# I2C_SW.net
KiCad netlist of a schematic drawn in Altium Designer
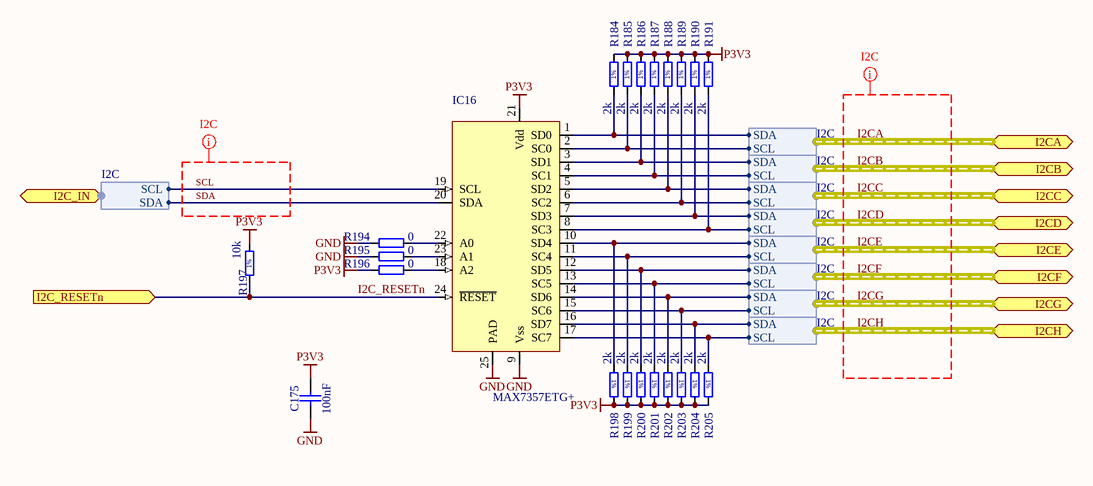
[diagram p0: I2C_SW.SchDoc]

(export (version "E")
  (design (tool "Eeschema 10.0.6"))
  (components
    (comp (ref "C175")
      (value "100nF")
      (footprint "CAPC1005X55N")
      (description "Non-polarised capacitor")
      (fields
        (field (name "PART NUMBER") "CC0402_100NF_16V_10%_X5R")
        (field (name "VOLTAGE") "16V")
        (field (name "AUTHOR") "CERN DEM JLC")
      )
      (libsource (lib "Capacitors") (part "Capacitor - non polarized"))
    )
    (comp (ref "IC16")
      (value "MAX7357ETG+")
      (footprint "HVQFN24")
      (description "8-channel I2C-bus multiplexer with reset, INT and timeout")
      (libsource (lib "LIBRARY_SCH") (part "IIC_MUX_MAX7357ETG+"))
    )
    (comp (ref "R184")
      (value "2k")
      (footprint "RESC1005X40N")
      (description "Resistor - 1%")
      (fields
        (field (name "PART NUMBER") "R0402_2K_1%_0.0625W_100PPM")
        (field (name "POWER") "0.0625W")
        (field (name "AUTHOR") "CERN DEM JLC")
      )
      (libsource (lib "Resistors") (part "Resistor - 1%"))
    )
    (comp (ref "R185")
      (value "2k")
      (footprint "RESC1005X40N")
      (description "Resistor - 1%")
      (fields
        (field (name "PART NUMBER") "R0402_2K_1%_0.0625W_100PPM")
        (field (name "POWER") "0.0625W")
        (field (name "AUTHOR") "CERN DEM JLC")
      )
      (libsource (lib "Resistors") (part "Resistor - 1%"))
    )
    (comp (ref "R186")
      (value "2k")
      (footprint "RESC1005X40N")
      (description "Resistor - 1%")
      (fields
        (field (name "PART NUMBER") "R0402_2K_1%_0.0625W_100PPM")
        (field (name "POWER") "0.0625W")
        (field (name "AUTHOR") "CERN DEM JLC")
      )
      (libsource (lib "Resistors") (part "Resistor - 1%"))
    )
    (comp (ref "R187")
      (value "2k")
      (footprint "RESC1005X40N")
      (description "Resistor - 1%")
      (fields
        (field (name "PART NUMBER") "R0402_2K_1%_0.0625W_100PPM")
        (field (name "POWER") "0.0625W")
        (field (name "AUTHOR") "CERN DEM JLC")
      )
      (libsource (lib "Resistors") (part "Resistor - 1%"))
    )
    (comp (ref "R188")
      (value "2k")
      (footprint "RESC1005X40N")
      (description "Resistor - 1%")
      (fields
        (field (name "PART NUMBER") "R0402_2K_1%_0.0625W_100PPM")
        (field (name "POWER") "0.0625W")
        (field (name "AUTHOR") "CERN DEM JLC")
      )
      (libsource (lib "Resistors") (part "Resistor - 1%"))
    )
    (comp (ref "R189")
      (value "2k")
      (footprint "RESC1005X40N")
      (description "Resistor - 1%")
      (fields
        (field (name "PART NUMBER") "R0402_2K_1%_0.0625W_100PPM")
        (field (name "POWER") "0.0625W")
        (field (name "AUTHOR") "CERN DEM JLC")
      )
      (libsource (lib "Resistors") (part "Resistor - 1%"))
    )
    (comp (ref "R190")
      (value "2k")
      (footprint "RESC1005X40N")
      (description "Resistor - 1%")
      (fields
        (field (name "PART NUMBER") "R0402_2K_1%_0.0625W_100PPM")
        (field (name "POWER") "0.0625W")
        (field (name "AUTHOR") "CERN DEM JLC")
      )
      (libsource (lib "Resistors") (part "Resistor - 1%"))
    )
    (comp (ref "R191")
      (value "2k")
      (footprint "RESC1005X40N")
      (description "Resistor - 1%")
      (fields
        (field (name "PART NUMBER") "R0402_2K_1%_0.0625W_100PPM")
        (field (name "POWER") "0.0625W")
        (field (name "AUTHOR") "CERN DEM JLC")
      )
      (libsource (lib "Resistors") (part "Resistor - 1%"))
    )
    (comp (ref "R194")
      (value "0")
      (footprint "RESC1005X40N")
      (description "Resistor")
      (fields
        (field (name "PART NUMBER") "R0402_0R_JUMPER")
        (field (name "MANUFACTURER") "GENERIC")
        (field (name "AUTHOR") "CERN DEM JLC")
      )
      (libsource (lib "Resistors") (part "Resistor"))
    )
    (comp (ref "R195")
      (value "0")
      (footprint "RESC1005X40N")
      (description "Resistor")
      (fields
        (field (name "PART NUMBER") "R0402_0R_JUMPER")
        (field (name "MANUFACTURER") "GENERIC")
        (field (name "AUTHOR") "CERN DEM JLC")
      )
      (libsource (lib "Resistors") (part "Resistor"))
    )
    (comp (ref "R196")
      (value "0")
      (footprint "RESC1005X40N")
      (description "Resistor")
      (fields
        (field (name "PART NUMBER") "R0402_0R_JUMPER")
        (field (name "MANUFACTURER") "GENERIC")
        (field (name "AUTHOR") "CERN DEM JLC")
      )
      (libsource (lib "Resistors") (part "Resistor"))
    )
    (comp (ref "R197")
      (value "10k")
      (footprint "RESC1005X40N")
      (description "Resistor - 1%")
      (fields
        (field (name "PART NUMBER") "R0402_10K_1%_0.0625W_100PPM")
        (field (name "POWER") "0.0625W")
        (field (name "AUTHOR") "CERN DEM JLC")
      )
      (libsource (lib "Resistors") (part "Resistor - 1%"))
    )
    (comp (ref "R198")
      (value "2k")
      (footprint "RESC1005X40N")
      (description "Resistor - 1%")
      (fields
        (field (name "PART NUMBER") "R0402_2K_1%_0.0625W_100PPM")
        (field (name "POWER") "0.0625W")
        (field (name "AUTHOR") "CERN DEM JLC")
      )
      (libsource (lib "Resistors") (part "Resistor - 1%"))
    )
    (comp (ref "R199")
      (value "2k")
      (footprint "RESC1005X40N")
      (description "Resistor - 1%")
      (fields
        (field (name "PART NUMBER") "R0402_2K_1%_0.0625W_100PPM")
        (field (name "POWER") "0.0625W")
        (field (name "AUTHOR") "CERN DEM JLC")
      )
      (libsource (lib "Resistors") (part "Resistor - 1%"))
    )
    (comp (ref "R200")
      (value "2k")
      (footprint "RESC1005X40N")
      (description "Resistor - 1%")
      (fields
        (field (name "PART NUMBER") "R0402_2K_1%_0.0625W_100PPM")
        (field (name "POWER") "0.0625W")
        (field (name "AUTHOR") "CERN DEM JLC")
      )
      (libsource (lib "Resistors") (part "Resistor - 1%"))
    )
    (comp (ref "R201")
      (value "2k")
      (footprint "RESC1005X40N")
      (description "Resistor - 1%")
      (fields
        (field (name "PART NUMBER") "R0402_2K_1%_0.0625W_100PPM")
        (field (name "POWER") "0.0625W")
        (field (name "AUTHOR") "CERN DEM JLC")
      )
      (libsource (lib "Resistors") (part "Resistor - 1%"))
    )
    (comp (ref "R202")
      (value "2k")
      (footprint "RESC1005X40N")
      (description "Resistor - 1%")
      (fields
        (field (name "PART NUMBER") "R0402_2K_1%_0.0625W_100PPM")
        (field (name "POWER") "0.0625W")
        (field (name "AUTHOR") "CERN DEM JLC")
      )
      (libsource (lib "Resistors") (part "Resistor - 1%"))
    )
    (comp (ref "R203")
      (value "2k")
      (footprint "RESC1005X40N")
      (description "Resistor - 1%")
      (fields
        (field (name "PART NUMBER") "R0402_2K_1%_0.0625W_100PPM")
        (field (name "POWER") "0.0625W")
        (field (name "AUTHOR") "CERN DEM JLC")
      )
      (libsource (lib "Resistors") (part "Resistor - 1%"))
    )
    (comp (ref "R204")
      (value "2k")
      (footprint "RESC1005X40N")
      (description "Resistor - 1%")
      (fields
        (field (name "PART NUMBER") "R0402_2K_1%_0.0625W_100PPM")
        (field (name "POWER") "0.0625W")
        (field (name "AUTHOR") "CERN DEM JLC")
      )
      (libsource (lib "Resistors") (part "Resistor - 1%"))
    )
    (comp (ref "R205")
      (value "2k")
      (footprint "RESC1005X40N")
      (description "Resistor - 1%")
      (fields
        (field (name "PART NUMBER") "R0402_2K_1%_0.0625W_100PPM")
        (field (name "POWER") "0.0625W")
        (field (name "AUTHOR") "CERN DEM JLC")
      )
      (libsource (lib "Resistors") (part "Resistor - 1%"))
    )
  )
  (nets
    (net (code "18") (name "/I2C_RESETn") (class "Default")
      (node (ref "IC16") (pin "24") (pinfunction "~{RESET}_24") (pintype "input"))
      (node (ref "R197") (pin "1") (pinfunction "1_1") (pintype "passive"))
    )
    (net (code "19") (name "/SCL") (class "Default")
      (node (ref "IC16") (pin "19") (pinfunction "SCL_19") (pintype "input"))
    )
    (net (code "20") (name "/SDA") (class "Default")
      (node (ref "IC16") (pin "20") (pinfunction "SDA_20") (pintype "bidirectional"))
    )
    (net (code "22") (name "GND") (class "Default")
      (node (ref "C175") (pin "1") (pinfunction "1_1") (pintype "passive"))
      (node (ref "IC16") (pin "25") (pinfunction "PAD_25") (pintype "power_in"))
      (node (ref "IC16") (pin "9") (pinfunction "Vss_9") (pintype "power_in"))
      (node (ref "R194") (pin "1") (pinfunction "1_1") (pintype "passive"))
      (node (ref "R195") (pin "1") (pinfunction "1_1") (pintype "passive"))
    )
    (net (code "23") (name "Net-(IC16-A0)") (class "Default")
      (node (ref "IC16") (pin "22") (pinfunction "A0_22") (pintype "input"))
      (node (ref "R194") (pin "2") (pinfunction "2_2") (pintype "passive"))
    )
    (net (code "24") (name "Net-(IC16-A1)") (class "Default")
      (node (ref "IC16") (pin "23") (pinfunction "A1_23") (pintype "input"))
      (node (ref "R195") (pin "2") (pinfunction "2_2") (pintype "passive"))
    )
    (net (code "25") (name "Net-(IC16-A2)") (class "Default")
      (node (ref "IC16") (pin "18") (pinfunction "A2_18") (pintype "input"))
      (node (ref "R196") (pin "2") (pinfunction "2_2") (pintype "passive"))
    )
    (net (code "26") (name "Net-(IC16-SC0)") (class "Default")
      (node (ref "IC16") (pin "2") (pinfunction "SC0_2") (pintype "bidirectional"))
      (node (ref "R185") (pin "1") (pinfunction "1_1") (pintype "passive"))
    )
    (net (code "27") (name "Net-(IC16-SC1)") (class "Default")
      (node (ref "IC16") (pin "4") (pinfunction "SC1_4") (pintype "bidirectional"))
      (node (ref "R187") (pin "1") (pinfunction "1_1") (pintype "passive"))
    )
    (net (code "28") (name "Net-(IC16-SC2)") (class "Default")
      (node (ref "IC16") (pin "6") (pinfunction "SC2_6") (pintype "bidirectional"))
      (node (ref "R189") (pin "1") (pinfunction "1_1") (pintype "passive"))
    )
    (net (code "29") (name "Net-(IC16-SC3)") (class "Default")
      (node (ref "IC16") (pin "8") (pinfunction "SC3_8") (pintype "bidirectional"))
      (node (ref "R191") (pin "1") (pinfunction "1_1") (pintype "passive"))
    )
    (net (code "30") (name "Net-(IC16-SC4)") (class "Default")
      (node (ref "IC16") (pin "11") (pinfunction "SC4_11") (pintype "bidirectional"))
      (node (ref "R199") (pin "1") (pinfunction "1_1") (pintype "passive"))
    )
    (net (code "31") (name "Net-(IC16-SC5)") (class "Default")
      (node (ref "IC16") (pin "13") (pinfunction "SC5_13") (pintype "bidirectional"))
      (node (ref "R201") (pin "1") (pinfunction "1_1") (pintype "passive"))
    )
    (net (code "32") (name "Net-(IC16-SC6)") (class "Default")
      (node (ref "IC16") (pin "15") (pinfunction "SC6_15") (pintype "bidirectional"))
      (node (ref "R203") (pin "1") (pinfunction "1_1") (pintype "passive"))
    )
    (net (code "33") (name "Net-(IC16-SC7)") (class "Default")
      (node (ref "IC16") (pin "17") (pinfunction "SC7_17") (pintype "bidirectional"))
      (node (ref "R205") (pin "1") (pinfunction "1_1") (pintype "passive"))
    )
    (net (code "34") (name "Net-(IC16-SD0)") (class "Default")
      (node (ref "IC16") (pin "1") (pinfunction "SD0_1") (pintype "bidirectional"))
      (node (ref "R184") (pin "1") (pinfunction "1_1") (pintype "passive"))
    )
    (net (code "35") (name "Net-(IC16-SD1)") (class "Default")
      (node (ref "IC16") (pin "3") (pinfunction "SD1_3") (pintype "bidirectional"))
      (node (ref "R186") (pin "1") (pinfunction "1_1") (pintype "passive"))
    )
    (net (code "36") (name "Net-(IC16-SD2)") (class "Default")
      (node (ref "IC16") (pin "5") (pinfunction "SD2_5") (pintype "bidirectional"))
      (node (ref "R188") (pin "1") (pinfunction "1_1") (pintype "passive"))
    )
    (net (code "37") (name "Net-(IC16-SD3)") (class "Default")
      (node (ref "IC16") (pin "7") (pinfunction "SD3_7") (pintype "bidirectional"))
      (node (ref "R190") (pin "1") (pinfunction "1_1") (pintype "passive"))
    )
    (net (code "38") (name "Net-(IC16-SD4)") (class "Default")
      (node (ref "IC16") (pin "10") (pinfunction "SD4_10") (pintype "bidirectional"))
      (node (ref "R198") (pin "1") (pinfunction "1_1") (pintype "passive"))
    )
    (net (code "39") (name "Net-(IC16-SD5)") (class "Default")
      (node (ref "IC16") (pin "12") (pinfunction "SD5_12") (pintype "bidirectional"))
      (node (ref "R200") (pin "1") (pinfunction "1_1") (pintype "passive"))
    )
    (net (code "40") (name "Net-(IC16-SD6)") (class "Default")
      (node (ref "IC16") (pin "14") (pinfunction "SD6_14") (pintype "bidirectional"))
      (node (ref "R202") (pin "1") (pinfunction "1_1") (pintype "passive"))
    )
    (net (code "41") (name "Net-(IC16-SD7)") (class "Default")
      (node (ref "IC16") (pin "16") (pinfunction "SD7_16") (pintype "bidirectional"))
      (node (ref "R204") (pin "1") (pinfunction "1_1") (pintype "passive"))
    )
    (net (code "42") (name "P3V3") (class "Default")
      (node (ref "C175") (pin "2") (pinfunction "2_2") (pintype "passive"))
      (node (ref "IC16") (pin "21") (pinfunction "Vdd_21") (pintype "power_in"))
      (node (ref "R184") (pin "2") (pinfunction "2_2") (pintype "passive"))
      (node (ref "R185") (pin "2") (pinfunction "2_2") (pintype "passive"))
      (node (ref "R186") (pin "2") (pinfunction "2_2") (pintype "passive"))
      (node (ref "R187") (pin "2") (pinfunction "2_2") (pintype "passive"))
      (node (ref "R188") (pin "2") (pinfunction "2_2") (pintype "passive"))
      (node (ref "R189") (pin "2") (pinfunction "2_2") (pintype "passive"))
      (node (ref "R190") (pin "2") (pinfunction "2_2") (pintype "passive"))
      (node (ref "R191") (pin "2") (pinfunction "2_2") (pintype "passive"))
      (node (ref "R196") (pin "1") (pinfunction "1_1") (pintype "passive"))
      (node (ref "R197") (pin "2") (pinfunction "2_2") (pintype "passive"))
      (node (ref "R198") (pin "2") (pinfunction "2_2") (pintype "passive"))
      (node (ref "R199") (pin "2") (pinfunction "2_2") (pintype "passive"))
      (node (ref "R200") (pin "2") (pinfunction "2_2") (pintype "passive"))
      (node (ref "R201") (pin "2") (pinfunction "2_2") (pintype "passive"))
      (node (ref "R202") (pin "2") (pinfunction "2_2") (pintype "passive"))
      (node (ref "R203") (pin "2") (pinfunction "2_2") (pintype "passive"))
      (node (ref "R204") (pin "2") (pinfunction "2_2") (pintype "passive"))
      (node (ref "R205") (pin "2") (pinfunction "2_2") (pintype "passive"))
    )
  )
)
